# Display_LCD16x2.net
KiCad netlist of a schematic drawn in Altium Designer
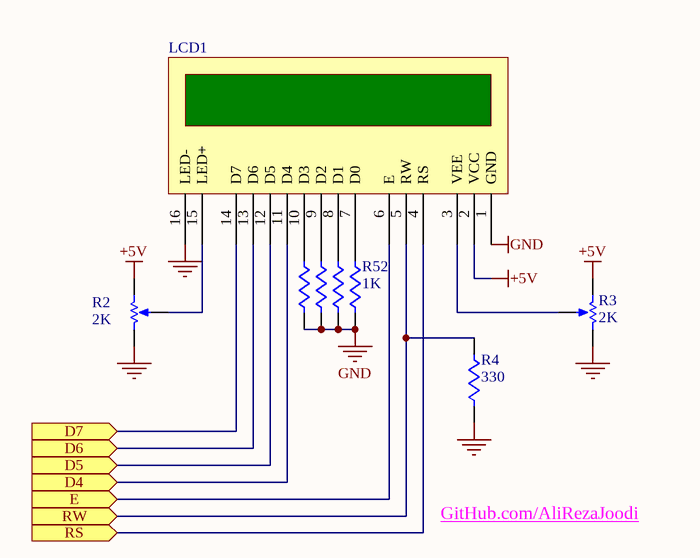
[diagram p0: Display_LCD16x2.SchDoc]

(export (version "E")
  (design (tool "Eeschema 10.0.6"))
  (components
    (comp (ref "LCD1")
      (value "LCD_16*2")
      (footprint "LCD_2x16")
      (libsource (lib "Miscellaneous Devices") (part "LCD_16*2"))
    )
    (comp (ref "R2")
      (value "2K")
      (footprint "VR8-5/5.6MM")
      (description "Potentiometer")
      (fields
        (field (name "MANUFACTURER") "Generic Components")
        (field (name "Comment") "RPot1")
        (field (name "PUBLISHER") "Altium Limited")
      )
      (libsource (lib "Miscellaneous Devices") (part "RPot1"))
    )
    (comp (ref "R3")
      (value "2K")
      (footprint "VR8-5/5.6MM")
      (description "Potentiometer")
      (fields
        (field (name "MANUFACTURER") "Generic Components")
        (field (name "Comment") "RPot1")
        (field (name "PUBLISHER") "Altium Limited")
      )
      (libsource (lib "Miscellaneous Devices") (part "RPot1"))
    )
    (comp (ref "R4")
      (value "330")
      (footprint "AXIAL-0.4")
      (description "Resistor")
      (fields
        (field (name "MANUFACTURER") "Generic Components")
        (field (name "Comment") "Res1")
        (field (name "PUBLISHER") "Altium Limited")
      )
      (libsource (lib "Miscellaneous Devices") (part "Res1"))
    )
    (comp (ref "R9")
      (value "Res1")
      (footprint "AXIAL-0.4")
      (description "Resistor")
      (fields (field (name "MANUFACTURER") "Generic Components") (field (name "PUBLISHER") "Altium Limited"))
      (libsource (lib "Miscellaneous Devices") (part "Res1"))
    )
    (comp (ref "R50")
      (value "Res1")
      (footprint "AXIAL-0.4")
      (description "Resistor")
      (fields (field (name "MANUFACTURER") "Generic Components") (field (name "PUBLISHER") "Altium Limited"))
      (libsource (lib "Miscellaneous Devices") (part "Res1"))
    )
    (comp (ref "R51")
      (value "Res1")
      (footprint "AXIAL-0.4")
      (description "Resistor")
      (fields (field (name "MANUFACTURER") "Generic Components") (field (name "PUBLISHER") "Altium Limited"))
      (libsource (lib "Miscellaneous Devices") (part "Res1"))
    )
    (comp (ref "R52")
      (value "1K")
      (footprint "AXIAL-0.4")
      (description "Resistor")
      (fields
        (field (name "MANUFACTURER") "Generic Components")
        (field (name "Comment") "Res1")
        (field (name "PUBLISHER") "Altium Limited")
      )
      (libsource (lib "Miscellaneous Devices") (part "Res1"))
    )
  )
  (nets
    (net (code "1") (name "+5V") (class "Default")
      (node (ref "LCD1") (pin "2") (pinfunction "VCC_2") (pintype "passive"))
      (node (ref "R2") (pin "1") (pinfunction "TOP_1") (pintype "passive"))
      (node (ref "R3") (pin "2") (pinfunction "BOT_2") (pintype "passive"))
    )
    (net (code "2") (name "/D4") (class "Default")
      (node (ref "LCD1") (pin "11") (pinfunction "D4_11") (pintype "passive"))
    )
    (net (code "3") (name "/D5") (class "Default")
      (node (ref "LCD1") (pin "12") (pinfunction "D5_12") (pintype "passive"))
    )
    (net (code "4") (name "/D6") (class "Default")
      (node (ref "LCD1") (pin "13") (pinfunction "D6_13") (pintype "passive"))
    )
    (net (code "5") (name "/D7") (class "Default")
      (node (ref "LCD1") (pin "14") (pinfunction "D7_14") (pintype "passive"))
    )
    (net (code "6") (name "/E") (class "Default")
      (node (ref "LCD1") (pin "6") (pinfunction "E_6") (pintype "passive"))
    )
    (net (code "7") (name "/RS") (class "Default")
      (node (ref "LCD1") (pin "4") (pinfunction "RS_4") (pintype "passive"))
    )
    (net (code "8") (name "/RW") (class "Default")
      (node (ref "LCD1") (pin "5") (pinfunction "RW_5") (pintype "passive"))
      (node (ref "R4") (pin "2") (pinfunction "2_2") (pintype "passive"))
    )
    (net (code "9") (name "GND") (class "Default")
      (node (ref "LCD1") (pin "1") (pinfunction "GND_1") (pintype "passive"))
      (node (ref "LCD1") (pin "16") (pinfunction "LED-_16") (pintype "passive"))
      (node (ref "R2") (pin "2") (pinfunction "BOT_2") (pintype "passive"))
      (node (ref "R3") (pin "1") (pinfunction "TOP_1") (pintype "passive"))
      (node (ref "R4") (pin "1") (pinfunction "1_1") (pintype "passive"))
      (node (ref "R50") (pin "1") (pinfunction "1_1") (pintype "passive"))
      (node (ref "R51") (pin "1") (pinfunction "1_1") (pintype "passive"))
      (node (ref "R52") (pin "1") (pinfunction "1_1") (pintype "passive"))
      (node (ref "R9") (pin "1") (pinfunction "1_1") (pintype "passive"))
    )
    (net (code "10") (name "Net-(LCD1-D0)") (class "Default")
      (node (ref "LCD1") (pin "7") (pinfunction "D0_7") (pintype "passive"))
      (node (ref "R52") (pin "2") (pinfunction "2_2") (pintype "passive"))
    )
    (net (code "11") (name "Net-(LCD1-D1)") (class "Default")
      (node (ref "LCD1") (pin "8") (pinfunction "D1_8") (pintype "passive"))
      (node (ref "R51") (pin "2") (pinfunction "2_2") (pintype "passive"))
    )
    (net (code "12") (name "Net-(LCD1-D2)") (class "Default")
      (node (ref "LCD1") (pin "9") (pinfunction "D2_9") (pintype "passive"))
      (node (ref "R50") (pin "2") (pinfunction "2_2") (pintype "passive"))
    )
    (net (code "13") (name "Net-(LCD1-D3)") (class "Default")
      (node (ref "LCD1") (pin "10") (pinfunction "D3_10") (pintype "passive"))
      (node (ref "R9") (pin "2") (pinfunction "2_2") (pintype "passive"))
    )
    (net (code "14") (name "Net-(LCD1-LED+)") (class "Default")
      (node (ref "LCD1") (pin "15") (pinfunction "LED+_15") (pintype "passive"))
      (node (ref "R2") (pin "3") (pinfunction "TAP_3") (pintype "passive"))
    )
    (net (code "15") (name "Net-(LCD1-VEE)") (class "Default")
      (node (ref "LCD1") (pin "3") (pinfunction "VEE_3") (pintype "passive"))
      (node (ref "R3") (pin "3") (pinfunction "TAP_3") (pintype "passive"))
    )
  )
)
